# BLUENRG-M2SA.net
KiCad netlist of a schematic drawn in Altium Designer
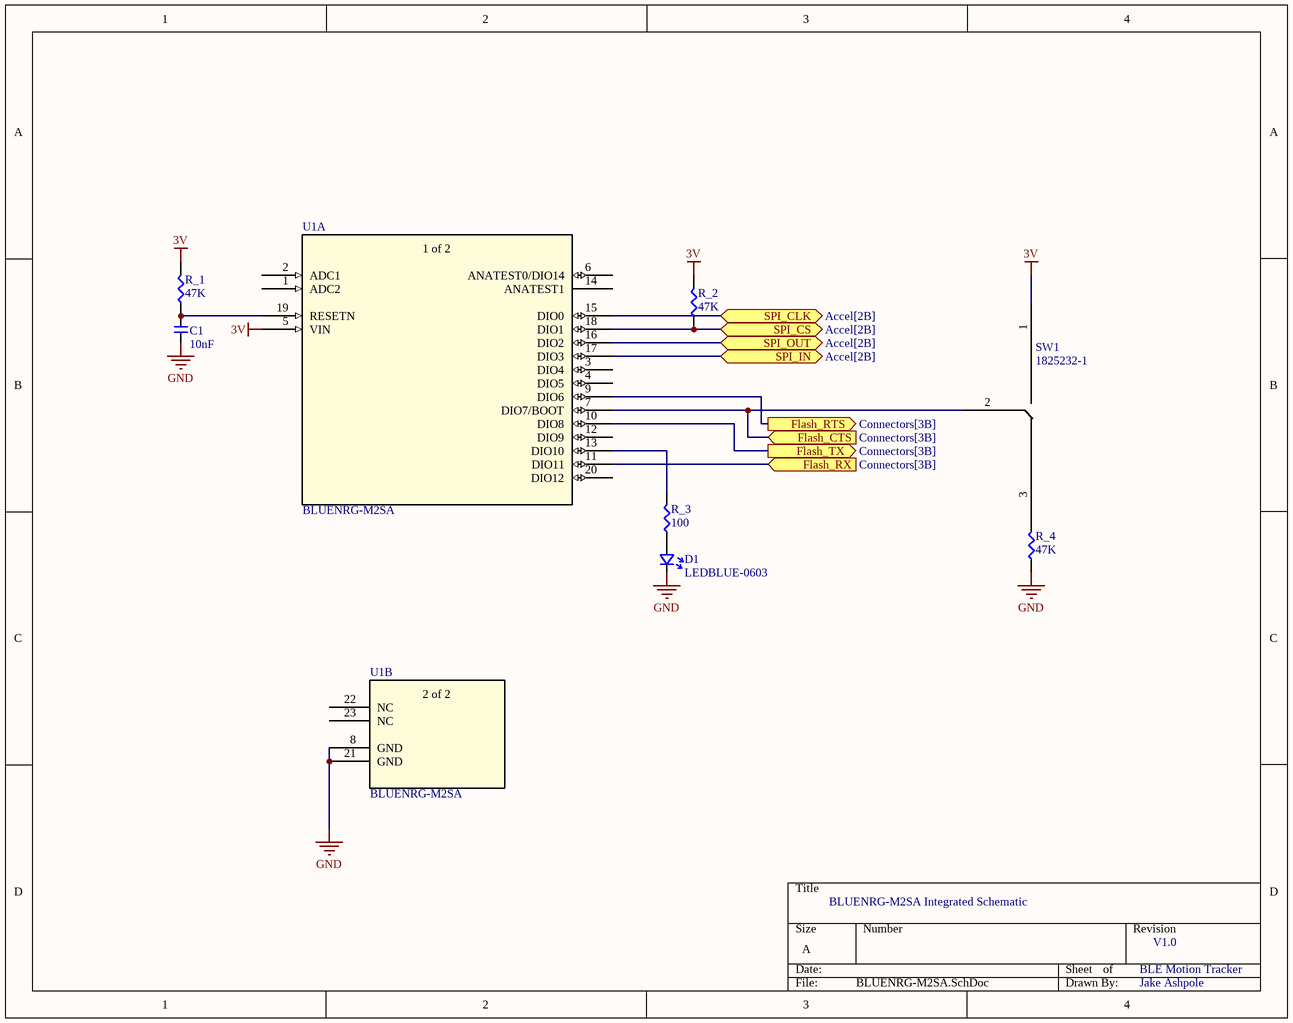
[diagram p0: BLUENRG-M2SA.SchDoc]

(export (version "E")
  (design (tool "Eeschema 10.0.6"))
  (components
    (comp (ref "C1")
      (value "10nF")
      (footprint "CAP-0603")
      (fields (field (name "SOURCE") "ife19_Elec_Library.SchLib"))
      (libsource (lib "Illini Formula Electric") (part "CAP-0603"))
    )
    (comp (ref "D1")
      (value "LEDBLUE-0603")
      (footprint "LEDBLUE-0603")
      (fields (field (name "SOURCE") "ife19_Elec_Library.SchLib"))
      (libsource (lib "Illini Formula Electric") (part "LEDBLUE-0603"))
    )
    (comp (ref "R_1")
      (value "47K")
      (footprint "RES-0603")
      (fields (field (name "SOURCE") "ife19_Elec_Library.SchLib"))
      (libsource (lib "Illini Formula Electric") (part "Symbol"))
    )
    (comp (ref "R_2")
      (value "47K")
      (footprint "RES-0603")
      (fields (field (name "SOURCE") "ife19_Elec_Library.SchLib"))
      (libsource (lib "Illini Formula Electric") (part "Symbol"))
    )
    (comp (ref "R_3")
      (value "100")
      (footprint "RES-0603")
      (fields (field (name "SOURCE") "ife19_Elec_Library.SchLib"))
      (libsource (lib "Illini Formula Electric") (part "Symbol"))
    )
    (comp (ref "R_4")
      (value "47K")
      (footprint "RES-0603")
      (fields (field (name "SOURCE") "ife19_Elec_Library.SchLib"))
      (libsource (lib "Illini Formula Electric") (part "Symbol"))
    )
    (comp (ref "SW1")
      (value "1825232-1")
      (footprint "1825232-1_TEC")
      (description "https://www.mouser.com/ProductDetail/655-1825232-1")
      (libsource (lib "1825232-1") (part "1825232-1"))
    )
    (comp (ref "U1")
      (value "BLUENRG-M2SA")
      (footprint "BLUENRG-2M_STM")
      (libsource (lib "BLUENRG-M2SA") (part "BLUENRG-M2SA"))
    )
  )
  (nets
    (net (code "1") (name "/Flash_CTS") (class "Default")
      (node (ref "SW1") (pin "2") (pinfunction "2_2") (pintype "passive"))
      (node (ref "U1") (pin "7") (pinfunction "DIO7/BOOT_7") (pintype "bidirectional"))
    )
    (net (code "2") (name "/Flash_RTS") (class "Default")
      (node (ref "U1") (pin "9") (pinfunction "DIO6_9") (pintype "bidirectional"))
    )
    (net (code "3") (name "/Flash_RX") (class "Default")
      (node (ref "U1") (pin "11") (pinfunction "DIO11_11") (pintype "bidirectional"))
    )
    (net (code "4") (name "/Flash_TX") (class "Default")
      (node (ref "U1") (pin "10") (pinfunction "DIO8_10") (pintype "bidirectional"))
    )
    (net (code "5") (name "/SPI_CLK") (class "Default")
      (node (ref "U1") (pin "15") (pinfunction "DIO0_15") (pintype "bidirectional"))
    )
    (net (code "6") (name "/SPI_CS") (class "Default")
      (node (ref "R_2") (pin "1") (pinfunction "1_1") (pintype "passive"))
      (node (ref "U1") (pin "18") (pinfunction "DIO1_18") (pintype "bidirectional"))
    )
    (net (code "7") (name "/SPI_IN") (class "Default")
      (node (ref "U1") (pin "17") (pinfunction "DIO3_17") (pintype "bidirectional"))
    )
    (net (code "8") (name "/SPI_OUT") (class "Default")
      (node (ref "U1") (pin "16") (pinfunction "DIO2_16") (pintype "bidirectional"))
    )
    (net (code "9") (name "3V") (class "Default")
      (node (ref "R_1") (pin "2") (pinfunction "2_2") (pintype "passive"))
      (node (ref "R_2") (pin "2") (pinfunction "2_2") (pintype "passive"))
      (node (ref "SW1") (pin "1") (pinfunction "1_1") (pintype "passive"))
      (node (ref "U1") (pin "5") (pinfunction "VIN_5") (pintype "input"))
    )
    (net (code "10") (name "GND") (class "Default")
      (node (ref "C1") (pin "1") (pinfunction "1_1") (pintype "passive"))
      (node (ref "D1") (pin "K") (pinfunction "K_K") (pintype "passive"))
      (node (ref "R_4") (pin "1") (pinfunction "1_1") (pintype "passive"))
      (node (ref "U1") (pin "21") (pinfunction "GND_21") (pintype "power_in"))
      (node (ref "U1") (pin "8") (pinfunction "GND_8") (pintype "power_in"))
    )
    (net (code "11") (name "Net-(D1-PadA)") (class "Default")
      (node (ref "D1") (pin "A") (pinfunction "A_A") (pintype "passive"))
      (node (ref "R_3") (pin "1") (pinfunction "1_1") (pintype "passive"))
    )
    (net (code "12") (name "Net-(R_4-Pad2)") (class "Default")
      (node (ref "R_4") (pin "2") (pinfunction "2_2") (pintype "passive"))
      (node (ref "SW1") (pin "3") (pinfunction "3_3") (pintype "passive"))
    )
    (net (code "13") (name "Net-(U1A-DIO10)") (class "Default")
      (node (ref "R_3") (pin "2") (pinfunction "2_2") (pintype "passive"))
      (node (ref "U1") (pin "13") (pinfunction "DIO10_13") (pintype "bidirectional"))
    )
    (net (code "14") (name "Net-(U1A-RESETN)") (class "Default")
      (node (ref "C1") (pin "2") (pinfunction "2_2") (pintype "passive"))
      (node (ref "R_1") (pin "1") (pinfunction "1_1") (pintype "passive"))
      (node (ref "U1") (pin "19") (pinfunction "RESETN_19") (pintype "input"))
    )
    (net (code "15") (name "unconnected-(U1A-ADC1-Pad2)") (class "Default")
      (node (ref "U1") (pin "2") (pinfunction "ADC1_2") (pintype "input"))
    )
    (net (code "16") (name "unconnected-(U1A-ADC2-Pad1)") (class "Default")
      (node (ref "U1") (pin "1") (pinfunction "ADC2_1") (pintype "input"))
    )
    (net (code "17") (name "unconnected-(U1A-ANATEST0{slash}DIO14-Pad6)") (class "Default")
      (node (ref "U1") (pin "6") (pinfunction "ANATEST0/DIO14_6") (pintype "bidirectional"))
    )
    (net (code "18") (name "unconnected-(U1A-ANATEST1-Pad14)") (class "Default")
      (node (ref "U1") (pin "14") (pinfunction "ANATEST1_14") (pintype "passive"))
    )
    (net (code "19") (name "unconnected-(U1A-DIO4-Pad3)") (class "Default")
      (node (ref "U1") (pin "3") (pinfunction "DIO4_3") (pintype "bidirectional"))
    )
    (net (code "20") (name "unconnected-(U1A-DIO5-Pad4)") (class "Default")
      (node (ref "U1") (pin "4") (pinfunction "DIO5_4") (pintype "bidirectional"))
    )
    (net (code "21") (name "unconnected-(U1A-DIO9-Pad12)") (class "Default")
      (node (ref "U1") (pin "12") (pinfunction "DIO9_12") (pintype "bidirectional"))
    )
    (net (code "22") (name "unconnected-(U1A-DIO12-Pad20)") (class "Default")
      (node (ref "U1") (pin "20") (pinfunction "DIO12_20") (pintype "bidirectional"))
    )
    (net (code "23") (name "unconnected-(U1B-NC-Pad22)") (class "Default")
      (node (ref "U1") (pin "22") (pinfunction "NC_22") (pintype "passive"))
    )
    (net (code "24") (name "unconnected-(U1B-NC-Pad23)") (class "Default")
      (node (ref "U1") (pin "23") (pinfunction "NC_23") (pintype "passive"))
    )
  )
)
